# ProPrj_SunLight.net
KiCad netlist of a schematic drawn in EasyEDA Pro
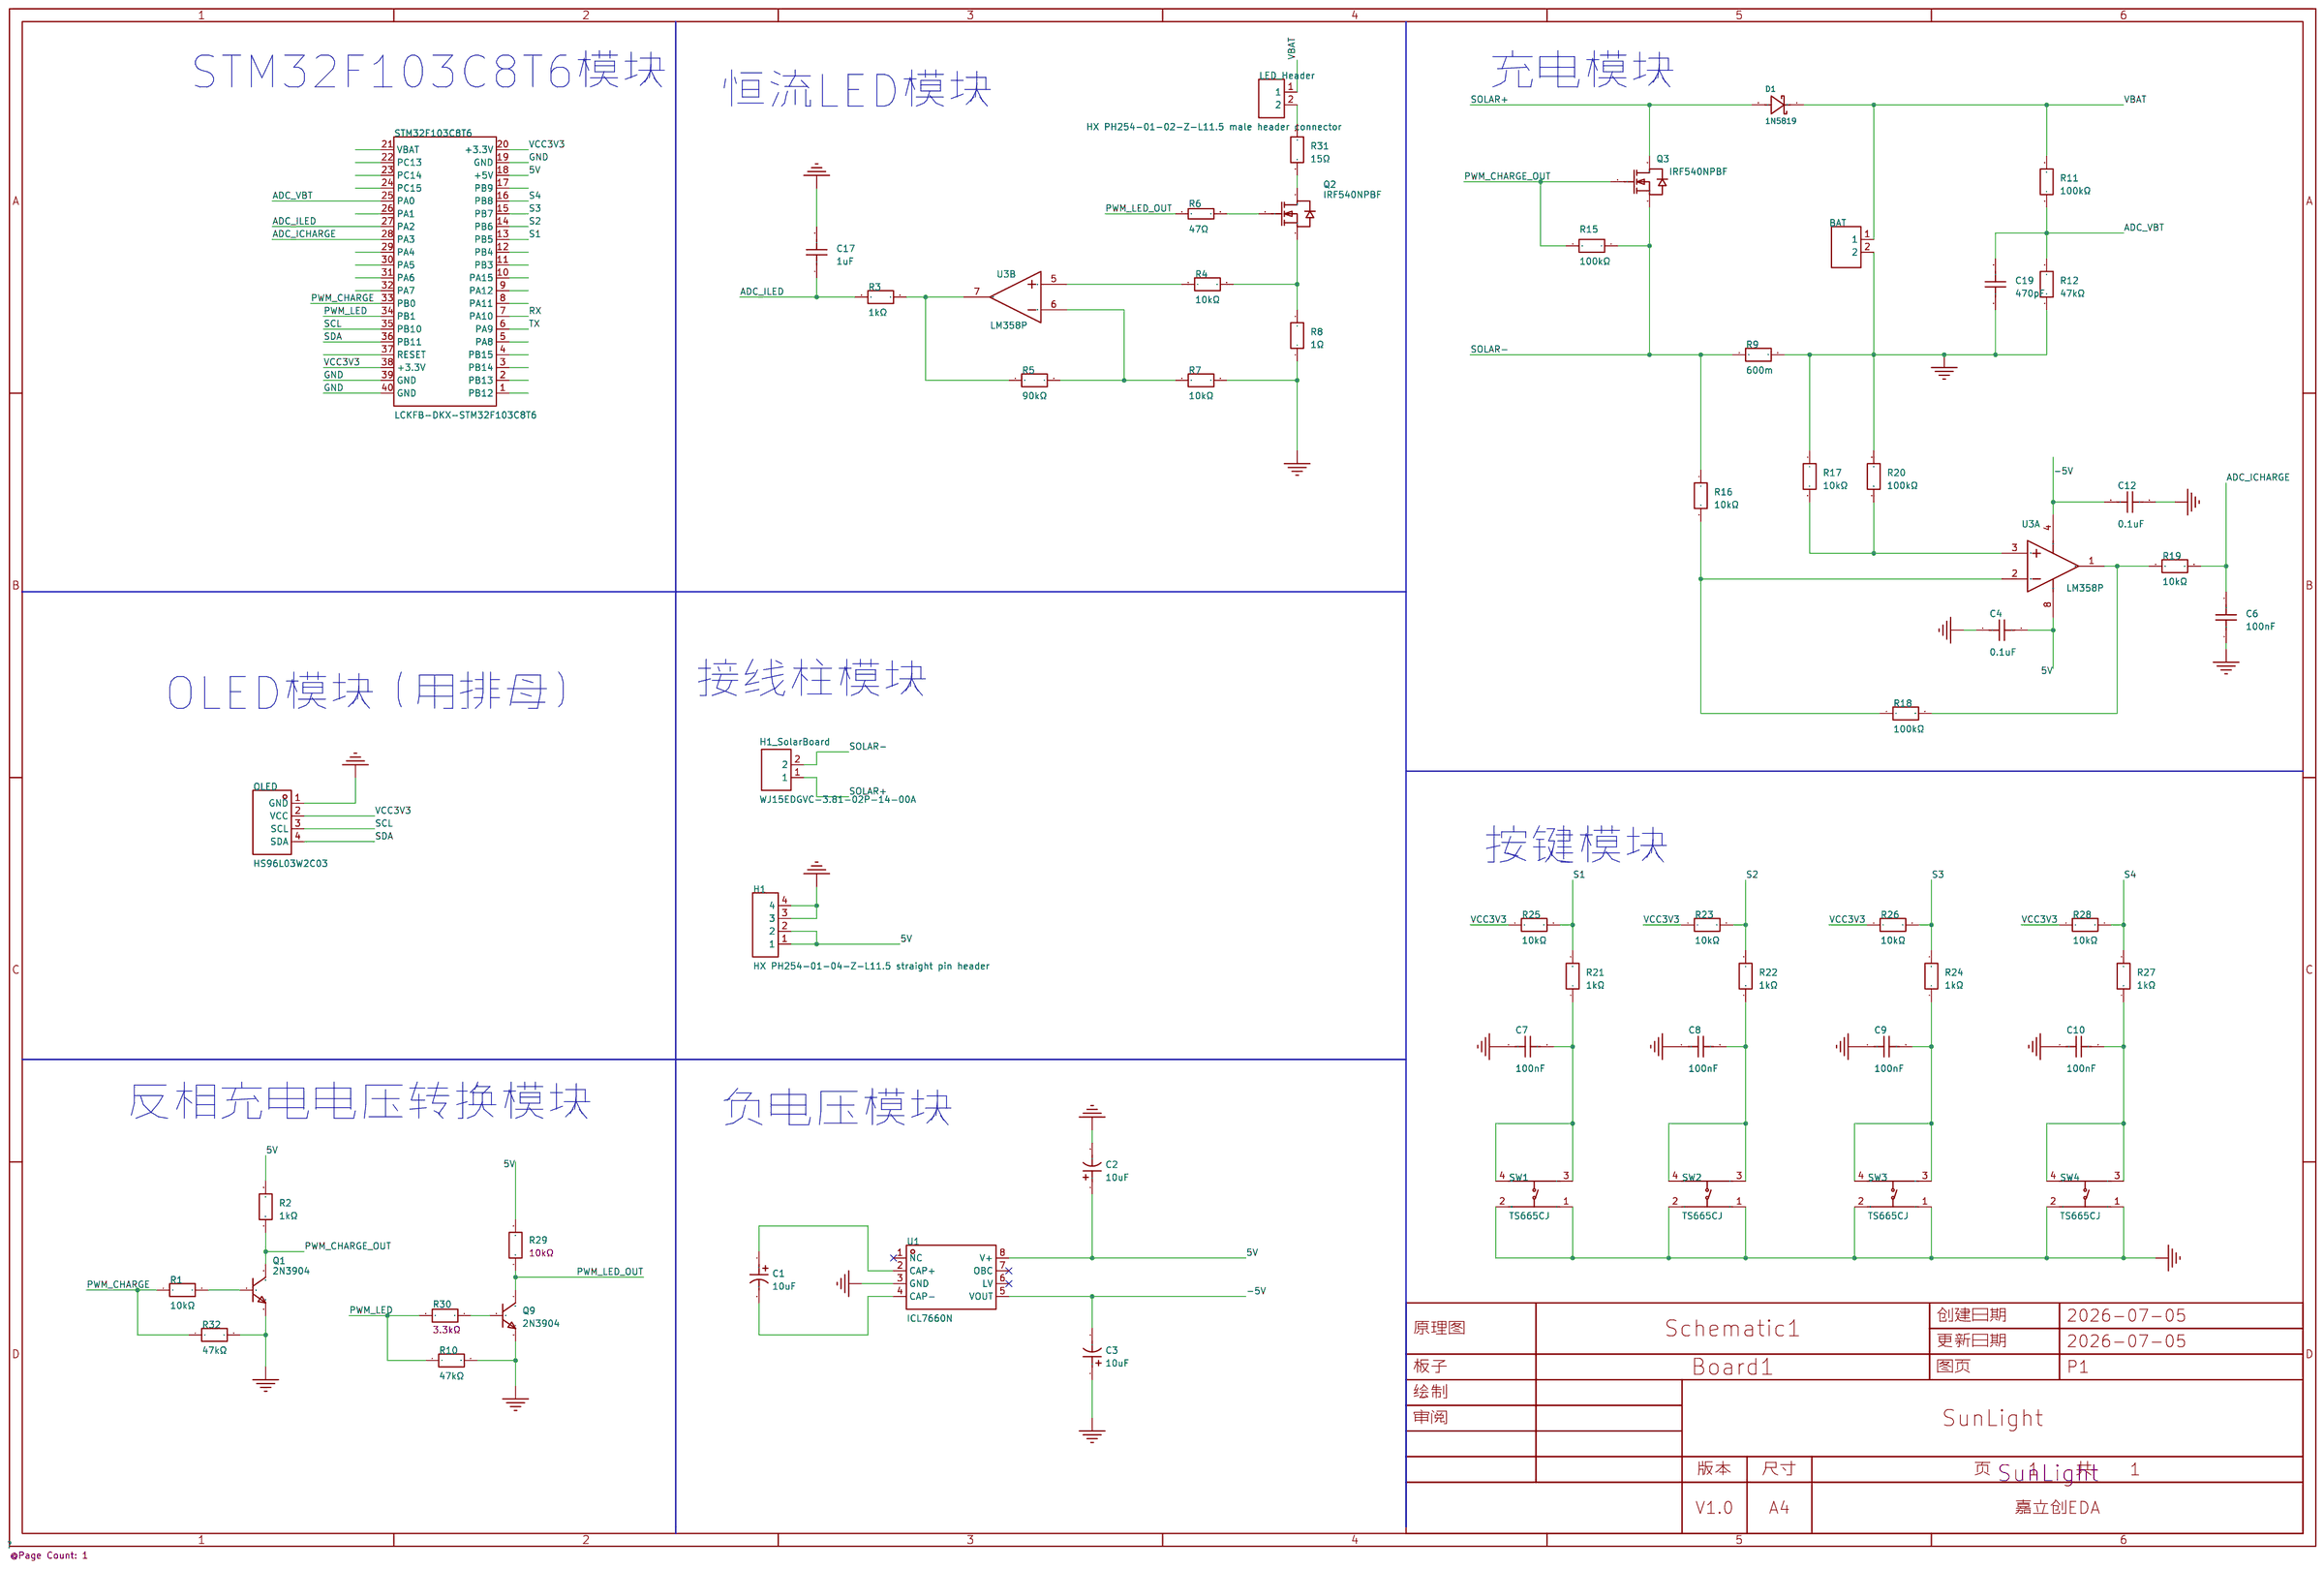
[diagram p0: schematic sheet]

(export (version "E")
  (design (tool "Eeschema 10.0.6"))
  (components
    (comp (ref "BAT")
      (value "WJ15EDGVC-3.81-02P-14-00A")
      (footprint "easyedapro:CONN-TH_WJ15EDGVC-3.81-2P")
      (fields (field (name "Manufacturer") "KANGNEX(康奈克斯电气)"))
      (libsource (lib "easyedapro") (part "WJ15EDGVC-3.81-2P"))
    )
    (comp (ref "C1")
      (value "10uF")
      (footprint "easyedapro:CAP-TH_BD10.0-P5.00-D0.6-FD_1")
      (fields (field (name "Manufacturer Part") "ERG450V10M10x16") (field (name "Manufacturer") "JIERR(捷而瑞)"))
      (libsource (lib "easyedapro") (part "ERG450V10M10X16"))
    )
    (comp (ref "C2")
      (value "10uF")
      (footprint "easyedapro:CAP-TH_BD10.0-P5.00-D0.6-FD_1")
      (fields (field (name "Manufacturer Part") "ERG450V10M10x16") (field (name "Manufacturer") "JIERR(捷而瑞)"))
      (libsource (lib "easyedapro") (part "ERG450V10M10X16"))
    )
    (comp (ref "C3")
      (value "10uF")
      (footprint "easyedapro:CAP-TH_BD10.0-P5.00-D0.6-FD_1")
      (fields (field (name "Manufacturer Part") "ERG450V10M10x16") (field (name "Manufacturer") "JIERR(捷而瑞)"))
      (libsource (lib "easyedapro") (part "ERG450V10M10X16"))
    )
    (comp (ref "C4")
      (value "0.1uF")
      (footprint "easyedapro:CAP-TH_L5.3-W3.2-P2.54-D0.6-S2.65")
      (description "容值:100nF;精度:-20%~+80%;额定电压:50V;温度系数:Y5V;")
      (fields
        (field (name "Manufacturer Part") "CC1H104ZA1ED3F5O1100")
        (field (name "Manufacturer") "Dersonic(德尔创)")
      )
      (libsource (lib "easyedapro") (part "CC1H104ZA1ED3F5O1100"))
    )
    (comp (ref "C6")
      (value "100nF")
      (footprint "easyedapro:CAP-TH_L5.5-W4.0-P5.00-D0.5")
      (fields
        (field (name "Manufacturer Part") "Y5P102K2KV16CC0224")
        (field (name "Manufacturer") "KNSCHA(科尼盛)")
      )
      (libsource (lib "easyedapro") (part "Y5P102K2KV16CC0224"))
    )
    (comp (ref "C7")
      (value "100nF")
      (footprint "easyedapro:CAP-TH_L5.5-W4.0-P5.00-D0.5")
      (fields
        (field (name "Manufacturer Part") "Y5P102K2KV16CC0224")
        (field (name "Manufacturer") "KNSCHA(科尼盛)")
      )
      (libsource (lib "easyedapro") (part "Y5P102K2KV16CC0224"))
    )
    (comp (ref "C8")
      (value "100nF")
      (footprint "easyedapro:CAP-TH_L5.5-W4.0-P5.00-D0.5")
      (fields
        (field (name "Manufacturer Part") "Y5P102K2KV16CC0224")
        (field (name "Manufacturer") "KNSCHA(科尼盛)")
      )
      (libsource (lib "easyedapro") (part "Y5P102K2KV16CC0224"))
    )
    (comp (ref "C9")
      (value "100nF")
      (footprint "easyedapro:CAP-TH_L5.5-W4.0-P5.00-D0.5")
      (fields
        (field (name "Manufacturer Part") "Y5P102K2KV16CC0224")
        (field (name "Manufacturer") "KNSCHA(科尼盛)")
      )
      (libsource (lib "easyedapro") (part "Y5P102K2KV16CC0224"))
    )
    (comp (ref "C10")
      (value "100nF")
      (footprint "easyedapro:CAP-TH_L5.5-W4.0-P5.00-D0.5")
      (fields
        (field (name "Manufacturer Part") "Y5P102K2KV16CC0224")
        (field (name "Manufacturer") "KNSCHA(科尼盛)")
      )
      (libsource (lib "easyedapro") (part "Y5P102K2KV16CC0224"))
    )
    (comp (ref "C12")
      (value "0.1uF")
      (footprint "easyedapro:CAP-TH_L5.3-W3.2-P2.54-D0.6-S2.65")
      (description "容值:100nF;精度:-20%~+80%;额定电压:50V;温度系数:Y5V;")
      (fields
        (field (name "Manufacturer Part") "CC1H104ZA1ED3F5O1100")
        (field (name "Manufacturer") "Dersonic(德尔创)")
      )
      (libsource (lib "easyedapro") (part "CC1H104ZA1ED3F5O1100"))
    )
    (comp (ref "C17")
      (value "1uF")
      (footprint "easyedapro:CAP-TH_L5.8-W2.8")
      (fields
        (field (name "Manufacturer Part") "CC1H104MC1FD3F6C10SA")
        (field (name "Manufacturer") "Dersonic(德尔创)")
      )
      (libsource (lib "easyedapro") (part "CC1H104MC1FD3F6C10SA"))
    )
    (comp (ref "C19")
      (value "470pF")
      (footprint "easyedapro:CAP-TH_L5.5-W4.0-P5.00-D0.5")
      (fields
        (field (name "Manufacturer Part") "Y5P102K2KV16CC0224")
        (field (name "Manufacturer") "KNSCHA(科尼盛)")
      )
      (libsource (lib "easyedapro") (part "Y5P102K2KV16CC0224"))
    )
    (comp (ref "D1")
      (value "1N5819")
      (footprint "easyedapro:DO-41_BD2.4-L4.7-P8.70-D0.9-RD")
      (fields (field (name "Manufacturer") "R+O(宏嘉诚)"))
      (libsource (lib "easyedapro") (part "1N5819_C54795756"))
    )
    (comp (ref "H1")
      (value "HX PH254-01-04-Z-L11.5 straight pin header")
      (footprint "easyedapro:HDR-TH_4P-HX-PH254-01-04-Z-L11.5")
      (fields (field (name "Manufacturer") "hanxia(韩下)"))
      (libsource (lib "easyedapro") (part "HX PH254-01-04-Z-L11.5 STRAIGHT PIN HEADER"))
    )
    (comp (ref "H1_SolarBoard")
      (value "WJ15EDGVC-3.81-02P-14-00A")
      (footprint "easyedapro:CONN-TH_WJ15EDGVC-3.81-2P")
      (fields (field (name "Manufacturer") "KANGNEX(康奈克斯电气)"))
      (libsource (lib "easyedapro") (part "WJ15EDGVC-3.81-2P"))
    )
    (comp (ref "LED_Header")
      (value "HX PH254-01-02-Z-L11.5 male header connector")
      (footprint "easyedapro:HDR-TH_2P-P2.54-V-M")
      (fields (field (name "Manufacturer") "hanxia(韩下)"))
      (libsource (lib "easyedapro") (part "HX PH254-01-02-Z-L11.5 MALE HEADER CONNECTOR"))
    )
    (comp (ref "OLED")
      (value "HS96L03W2C03")
      (footprint "easyedapro:OLED-TH_L27.8-W27.2-P2.54_C9900033791")
      (description "核心芯片:SSD1315芯片;接口类型:I2C;尺寸(inch):0.96;像素分辨率:128x64;")
      (fields (field (name "Manufacturer") "HS(汉昇)"))
      (libsource (lib "easyedapro") (part "HS96L03W2C03"))
    )
    (comp (ref "Q1")
      (value "2N3904")
      (footprint "easyedapro:TO-92-3_L4.6-W3.6-P1.27-L_1")
      (fields (field (name "Manufacturer") "JSMSEMI(杰盛微)"))
      (libsource (lib "easyedapro") (part "2N3904_C2874602"))
    )
    (comp (ref "Q2")
      (value "IRF540NPBF")
      (footprint "easyedapro:TO-220-3_L10.0-W4.5-P2.54-L")
      (fields (field (name "Manufacturer") "Infineon(英飞凌)"))
      (libsource (lib "easyedapro") (part "IRF540NPBF"))
    )
    (comp (ref "Q3")
      (value "IRF540NPBF")
      (footprint "easyedapro:TO-220-3_L10.0-W4.5-P2.54-L")
      (fields (field (name "Manufacturer") "Infineon(英飞凌)"))
      (libsource (lib "easyedapro") (part "IRF540NPBF"))
    )
    (comp (ref "Q9")
      (value "2N3904")
      (footprint "easyedapro:TO-92-3_L4.6-W3.6-P1.27-L_1")
      (description "晶体管类型:NPN;集电极电流(Ic):200mA;集射极击穿电压(Vceo):40V;耗散功率(Pd):625mW;直流电流增益(hFE):-;")
      (fields (field (name "Manufacturer") "JSMSEMI(杰盛微)"))
      (libsource (lib "easyedapro") (part "2N3904_C2874602"))
    )
    (comp (ref "R1")
      (value "10kΩ")
      (footprint "easyedapro:RES-TH_BD2.7-L6.2-P10.20-D0.4")
      (description "电阻类型:金属膜电阻;阻值:1kΩ;精度:±1%;功率:250mW;温度系数:±100ppm/℃;")
      (fields (field (name "Manufacturer Part") "MF1/4W-1K±1%-ST52") (field (name "Manufacturer") "VO(翔胜)"))
      (libsource (lib "easyedapro") (part "MF1/4W-1K±1%-ST52"))
    )
    (comp (ref "R2")
      (value "1kΩ")
      (footprint "easyedapro:RES-TH_BD2.7-L6.2-P10.20-D0.4")
      (description "电阻类型:金属膜电阻;阻值:1kΩ;精度:±1%;功率:250mW;温度系数:±100ppm/℃;")
      (fields (field (name "Manufacturer Part") "MF1/4W-1K±1%-ST52") (field (name "Manufacturer") "VO(翔胜)"))
      (libsource (lib "easyedapro") (part "MF1/4W-1K±1%-ST52"))
    )
    (comp (ref "R3")
      (value "1kΩ")
      (footprint "easyedapro:RES-TH_BD2.7-L6.2-P10.20-D0.4")
      (description "电阻类型:金属膜电阻;阻值:1kΩ;精度:±1%;功率:250mW;温度系数:±100ppm/℃;")
      (fields (field (name "Manufacturer Part") "MF1/4W-1K±1%-ST52") (field (name "Manufacturer") "VO(翔胜)"))
      (libsource (lib "easyedapro") (part "MF1/4W-1K±1%-ST52"))
    )
    (comp (ref "R4")
      (value "10kΩ")
      (footprint "easyedapro:RES-TH_BD2.7-L6.2-P10.20-D0.4")
      (description "电阻类型:金属膜电阻;阻值:1kΩ;精度:±1%;功率:250mW;温度系数:±100ppm/℃;")
      (fields (field (name "Manufacturer Part") "MF1/4W-1K±1%-ST52") (field (name "Manufacturer") "VO(翔胜)"))
      (libsource (lib "easyedapro") (part "MF1/4W-1K±1%-ST52"))
    )
    (comp (ref "R5")
      (value "90kΩ")
      (footprint "easyedapro:RES-TH_BD2.7-L6.2-P10.20-D0.4")
      (description "电阻类型:金属膜电阻;阻值:1kΩ;精度:±1%;功率:250mW;温度系数:±100ppm/℃;")
      (fields (field (name "Manufacturer Part") "MF1/4W-1K±1%-ST52") (field (name "Manufacturer") "VO(翔胜)"))
      (libsource (lib "easyedapro") (part "MF1/4W-1K±1%-ST52"))
    )
    (comp (ref "R6")
      (value "47Ω")
      (footprint "easyedapro:RES-TH_BD2.4-L6.3-P10.30-D0.6")
      (fields (field (name "Manufacturer Part") "MFR-25FTE52-47R") (field (name "Manufacturer") "YAGEO(国巨)"))
      (libsource (lib "easyedapro") (part "MFR-25FTE52-47R"))
    )
    (comp (ref "R7")
      (value "10kΩ")
      (footprint "easyedapro:RES-TH_BD2.7-L6.2-P10.20-D0.4")
      (description "电阻类型:金属膜电阻;阻值:1kΩ;精度:±1%;功率:250mW;温度系数:±100ppm/℃;")
      (fields (field (name "Manufacturer Part") "MF1/4W-1K±1%-ST52") (field (name "Manufacturer") "VO(翔胜)"))
      (libsource (lib "easyedapro") (part "MF1/4W-1K±1%-ST52"))
    )
    (comp (ref "R8")
      (value "1Ω")
      (footprint "easyedapro:RES-TH_BD2.7-L6.2-P10.20-D0.4")
      (description "电阻类型:金属膜电阻;阻值:1kΩ;精度:±1%;功率:250mW;温度系数:±100ppm/℃;")
      (fields (field (name "Manufacturer Part") "MF1/4W-1K±1%-ST52") (field (name "Manufacturer") "VO(翔胜)"))
      (libsource (lib "easyedapro") (part "MF1/4W-1K±1%-ST52"))
    )
    (comp (ref "R9")
      (value "600m")
      (footprint "easyedapro:RES-TH_BD2.7-L6.2-P10.20-D0.4")
      (description "电阻类型:金属膜电阻;阻值:1kΩ;精度:±1%;功率:250mW;温度系数:±100ppm/℃;")
      (fields (field (name "Manufacturer Part") "MF1/4W-1K±1%-ST52") (field (name "Manufacturer") "VO(翔胜)"))
      (libsource (lib "easyedapro") (part "MF1/4W-1K±1%-ST52"))
    )
    (comp (ref "R10")
      (value "47kΩ")
      (footprint "easyedapro:RES-TH_BD2.7-L6.2-P10.20-D0.4")
      (fields (field (name "Manufacturer Part") "MF1/4W-47K±1%-ST52") (field (name "Manufacturer") "VO(翔胜)"))
      (libsource (lib "easyedapro") (part "MF1/4W-47K±1%-ST52"))
    )
    (comp (ref "R11")
      (value "100kΩ")
      (footprint "easyedapro:RES-TH_BD2.7-L6.2-P10.20-D0.4")
      (description "电阻类型:金属膜电阻;阻值:1kΩ;精度:±1%;功率:250mW;温度系数:±100ppm/℃;")
      (fields (field (name "Manufacturer Part") "MF1/4W-1K±1%-ST52") (field (name "Manufacturer") "VO(翔胜)"))
      (libsource (lib "easyedapro") (part "MF1/4W-1K±1%-ST52"))
    )
    (comp (ref "R12")
      (value "47kΩ")
      (footprint "easyedapro:RES-TH_BD2.7-L6.2-P10.20-D0.4")
      (description "电阻类型:金属膜电阻;阻值:1kΩ;精度:±1%;功率:250mW;温度系数:±100ppm/℃;")
      (fields (field (name "Manufacturer Part") "MF1/4W-1K±1%-ST52") (field (name "Manufacturer") "VO(翔胜)"))
      (libsource (lib "easyedapro") (part "MF1/4W-1K±1%-ST52"))
    )
    (comp (ref "R15")
      (value "100kΩ")
      (footprint "easyedapro:RES-TH_BD2.7-L6.2-P10.20-D0.4")
      (description "电阻类型:金属膜电阻;阻值:1kΩ;精度:±1%;功率:250mW;温度系数:±100ppm/℃;")
      (fields (field (name "Manufacturer Part") "MF1/4W-1K±1%-ST52") (field (name "Manufacturer") "VO(翔胜)"))
      (libsource (lib "easyedapro") (part "MF1/4W-1K±1%-ST52"))
    )
    (comp (ref "R16")
      (value "10kΩ")
      (footprint "easyedapro:RES-TH_BD2.7-L6.2-P10.20-D0.4")
      (description "电阻类型:金属膜电阻;阻值:1kΩ;精度:±1%;功率:250mW;温度系数:±100ppm/℃;")
      (fields (field (name "Manufacturer Part") "MF1/4W-1K±1%-ST52") (field (name "Manufacturer") "VO(翔胜)"))
      (libsource (lib "easyedapro") (part "MF1/4W-1K±1%-ST52"))
    )
    (comp (ref "R17")
      (value "10kΩ")
      (footprint "easyedapro:RES-TH_BD2.7-L6.2-P10.20-D0.4")
      (description "电阻类型:金属膜电阻;阻值:1kΩ;精度:±1%;功率:250mW;温度系数:±100ppm/℃;")
      (fields (field (name "Manufacturer Part") "MF1/4W-1K±1%-ST52") (field (name "Manufacturer") "VO(翔胜)"))
      (libsource (lib "easyedapro") (part "MF1/4W-1K±1%-ST52"))
    )
    (comp (ref "R18")
      (value "100kΩ")
      (footprint "easyedapro:RES-TH_BD2.7-L6.2-P10.20-D0.4")
      (description "电阻类型:金属膜电阻;阻值:1kΩ;精度:±1%;功率:250mW;温度系数:±100ppm/℃;")
      (fields (field (name "Manufacturer Part") "MF1/4W-1K±1%-ST52") (field (name "Manufacturer") "VO(翔胜)"))
      (libsource (lib "easyedapro") (part "MF1/4W-1K±1%-ST52"))
    )
    (comp (ref "R19")
      (value "10kΩ")
      (footprint "easyedapro:RES-TH_BD2.7-L6.2-P10.20-D0.4")
      (description "电阻类型:金属膜电阻;阻值:1kΩ;精度:±1%;功率:250mW;温度系数:±100ppm/℃;")
      (fields (field (name "Manufacturer Part") "MF1/4W-1K±1%-ST52") (field (name "Manufacturer") "VO(翔胜)"))
      (libsource (lib "easyedapro") (part "MF1/4W-1K±1%-ST52"))
    )
    (comp (ref "R20")
      (value "100kΩ")
      (footprint "easyedapro:RES-TH_BD2.7-L6.2-P10.20-D0.4")
      (description "电阻类型:金属膜电阻;阻值:1kΩ;精度:±1%;功率:250mW;温度系数:±100ppm/℃;")
      (fields (field (name "Manufacturer Part") "MF1/4W-1K±1%-ST52") (field (name "Manufacturer") "VO(翔胜)"))
      (libsource (lib "easyedapro") (part "MF1/4W-1K±1%-ST52"))
    )
    (comp (ref "R21")
      (value "1kΩ")
      (footprint "easyedapro:RES-TH_BD2.7-L6.2-P10.20-D0.4")
      (description "电阻类型:金属膜电阻;阻值:1kΩ;精度:±1%;功率:250mW;温度系数:±100ppm/℃;")
      (fields (field (name "Manufacturer Part") "MF1/4W-1K±1%-ST52") (field (name "Manufacturer") "VO(翔胜)"))
      (libsource (lib "easyedapro") (part "MF1/4W-1K±1%-ST52"))
    )
    (comp (ref "R22")
      (value "1kΩ")
      (footprint "easyedapro:RES-TH_BD2.7-L6.2-P10.20-D0.4")
      (description "电阻类型:金属膜电阻;阻值:1kΩ;精度:±1%;功率:250mW;温度系数:±100ppm/℃;")
      (fields (field (name "Manufacturer Part") "MF1/4W-1K±1%-ST52") (field (name "Manufacturer") "VO(翔胜)"))
      (libsource (lib "easyedapro") (part "MF1/4W-1K±1%-ST52"))
    )
    (comp (ref "R23")
      (value "10kΩ")
      (footprint "easyedapro:RES-TH_BD2.7-L6.2-P10.20-D0.4")
      (description "电阻类型:金属膜电阻;阻值:1kΩ;精度:±1%;功率:250mW;温度系数:±100ppm/℃;")
      (fields (field (name "Manufacturer Part") "MF1/4W-1K±1%-ST52") (field (name "Manufacturer") "VO(翔胜)"))
      (libsource (lib "easyedapro") (part "MF1/4W-1K±1%-ST52"))
    )
    (comp (ref "R24")
      (value "1kΩ")
      (footprint "easyedapro:RES-TH_BD2.7-L6.2-P10.20-D0.4")
      (description "电阻类型:金属膜电阻;阻值:1kΩ;精度:±1%;功率:250mW;温度系数:±100ppm/℃;")
      (fields (field (name "Manufacturer Part") "MF1/4W-1K±1%-ST52") (field (name "Manufacturer") "VO(翔胜)"))
      (libsource (lib "easyedapro") (part "MF1/4W-1K±1%-ST52"))
    )
    (comp (ref "R25")
      (value "10kΩ")
      (footprint "easyedapro:RES-TH_BD2.7-L6.2-P10.20-D0.4")
      (description "电阻类型:金属膜电阻;阻值:1kΩ;精度:±1%;功率:250mW;温度系数:±100ppm/℃;")
      (fields (field (name "Manufacturer Part") "MF1/4W-1K±1%-ST52") (field (name "Manufacturer") "VO(翔胜)"))
      (libsource (lib "easyedapro") (part "MF1/4W-1K±1%-ST52"))
    )
    (comp (ref "R26")
      (value "10kΩ")
      (footprint "easyedapro:RES-TH_BD2.7-L6.2-P10.20-D0.4")
      (description "电阻类型:金属膜电阻;阻值:1kΩ;精度:±1%;功率:250mW;温度系数:±100ppm/℃;")
      (fields (field (name "Manufacturer Part") "MF1/4W-1K±1%-ST52") (field (name "Manufacturer") "VO(翔胜)"))
      (libsource (lib "easyedapro") (part "MF1/4W-1K±1%-ST52"))
    )
    (comp (ref "R27")
      (value "1kΩ")
      (footprint "easyedapro:RES-TH_BD2.7-L6.2-P10.20-D0.4")
      (description "电阻类型:金属膜电阻;阻值:1kΩ;精度:±1%;功率:250mW;温度系数:±100ppm/℃;")
      (fields (field (name "Manufacturer Part") "MF1/4W-1K±1%-ST52") (field (name "Manufacturer") "VO(翔胜)"))
      (libsource (lib "easyedapro") (part "MF1/4W-1K±1%-ST52"))
    )
    (comp (ref "R28")
      (value "10kΩ")
      (footprint "easyedapro:RES-TH_BD2.7-L6.2-P10.20-D0.4")
      (description "电阻类型:金属膜电阻;阻值:1kΩ;精度:±1%;功率:250mW;温度系数:±100ppm/℃;")
      (fields (field (name "Manufacturer Part") "MF1/4W-1K±1%-ST52") (field (name "Manufacturer") "VO(翔胜)"))
      (libsource (lib "easyedapro") (part "MF1/4W-1K±1%-ST52"))
    )
    (comp (ref "R29")
      (value "1kΩ")
      (footprint "easyedapro:RES-TH_BD2.7-L6.2-P10.20-D0.4")
      (description "电阻类型:金属膜电阻;阻值:1kΩ;精度:±1%;功率:250mW;温度系数:±100ppm/℃;")
      (fields
        (field (name "Manufacturer Part") "MF1/4W-1K±1%-ST52")
        (field (name "Manufacturer") "VO(翔胜)")
        (field (name "Resistance") "10kΩ")
      )
      (libsource (lib "easyedapro") (part "MF1/4W-1K±1%-ST52"))
    )
    (comp (ref "R30")
      (value "1kΩ")
      (footprint "easyedapro:RES-TH_BD2.7-L6.2-P10.20-D0.4")
      (description "电阻类型:金属膜电阻;阻值:1kΩ;精度:±1%;功率:250mW;温度系数:±100ppm/℃;")
      (fields
        (field (name "Manufacturer Part") "MF1/4W-1K±1%-ST52")
        (field (name "Manufacturer") "VO(翔胜)")
        (field (name "Resistance") "3.3kΩ")
      )
      (libsource (lib "easyedapro") (part "MF1/4W-1K±1%-ST52"))
    )
    (comp (ref "R31")
      (value "15Ω")
      (footprint "easyedapro:RES-TH_BD2.7-L6.2-P10.20-D0.4")
      (fields (field (name "Manufacturer Part") "MF1/4W-4Ω7±1%-OT26") (field (name "Manufacturer") "VO(翔胜)"))
      (libsource (lib "easyedapro") (part "MF1/4W-4Ω7±1%-OT26"))
    )
    (comp (ref "R32")
      (value "47kΩ")
      (footprint "easyedapro:RES-TH_BD2.7-L6.2-P10.20-D0.4")
      (fields (field (name "Manufacturer Part") "MF1/4W-47K±1%-ST52") (field (name "Manufacturer") "VO(翔胜)"))
      (libsource (lib "easyedapro") (part "MF1/4W-47K±1%-ST52"))
    )
    (comp (ref "STM32F103C8T6")
      (value "LCKFB-DKX-STM32F103C8T6")
      (footprint "easyedapro:CONN-TH_L53.3-W22.9_STM32F103C8T6-CARD")
      (fields (field (name "Manufacturer") "立创开发板"))
      (libsource (lib "easyedapro") (part "LCKFB-DKX-STM32F103C8T6"))
    )
    (comp (ref "SW1")
      (value "TS665CJ")
      (footprint "easyedapro:SW-TH_4P-L6.0-W6.0-P4.50-LS6.5")
      (fields (field (name "Manufacturer") "SHOU HAN(首韩)"))
      (libsource (lib "easyedapro") (part "TS665CJ"))
    )
    (comp (ref "SW2")
      (value "TS665CJ")
      (footprint "easyedapro:SW-TH_4P-L6.0-W6.0-P4.50-LS6.5")
      (fields (field (name "Manufacturer") "SHOU HAN(首韩)"))
      (libsource (lib "easyedapro") (part "TS665CJ"))
    )
    (comp (ref "SW3")
      (value "TS665CJ")
      (footprint "easyedapro:SW-TH_4P-L6.0-W6.0-P4.50-LS6.5")
      (fields (field (name "Manufacturer") "SHOU HAN(首韩)"))
      (libsource (lib "easyedapro") (part "TS665CJ"))
    )
    (comp (ref "SW4")
      (value "TS665CJ")
      (footprint "easyedapro:SW-TH_4P-L6.0-W6.0-P4.50-LS6.5")
      (fields (field (name "Manufacturer") "SHOU HAN(首韩)"))
      (libsource (lib "easyedapro") (part "TS665CJ"))
    )
    (comp (ref "U1")
      (value "ICL7660N")
      (footprint "easyedapro:DIP-8_L9.4-W6.4-P2.54-LS9.1-BL")
      (fields (field (name "Manufacturer") "HGSEMI(华冠)"))
      (libsource (lib "easyedapro") (part "ICL7660N"))
    )
    (comp (ref "U3")
      (value "LM358P")
      (footprint "easyedapro:DIP-8_L9.7-W6.4-P2.54-LS7.6-BL")
      (description "放大器数:2;轨到轨:-;增益带宽积(GBW):1MHz;输入失调电压(Vos):2mV;压摆率(SR):-;输入偏置电流(Ib):45nA;")
      (fields (field (name "Manufacturer") "Slkor(萨科微)"))
      (libsource (lib "easyedapro") (part "LM358P_C5330384"))
    )
  )
  (nets
    (net (code "1") (name "/-5V") (class "Default")
      (node (ref "C12") (pin "2") (pinfunction "2_2") (pintype "unspecified"))
      (node (ref "C3") (pin "2") (pinfunction "2_2") (pintype "input"))
      (node (ref "U1") (pin "5") (pinfunction "VOUT_5") (pintype "unspecified"))
      (node (ref "U3") (pin "4") (pinfunction "GND_4") (pintype "unspecified"))
    )
    (net (code "2") (name "/5V") (class "Default")
      (node (ref "C2") (pin "1") (pinfunction "1_1") (pintype "input"))
      (node (ref "C4") (pin "2") (pinfunction "2_2") (pintype "unspecified"))
      (node (ref "H1") (pin "1") (pinfunction "1_1") (pintype "unspecified"))
      (node (ref "H1") (pin "2") (pinfunction "2_2") (pintype "unspecified"))
      (node (ref "R2") (pin "2") (pinfunction "2_2") (pintype "unspecified"))
      (node (ref "R29") (pin "2") (pinfunction "2_2") (pintype "unspecified"))
      (node (ref "STM32F103C8T6") (pin "18") (pinfunction "+5V_18") (pintype "unspecified"))
      (node (ref "U1") (pin "8") (pinfunction "V+_8") (pintype "unspecified"))
      (node (ref "U3") (pin "8") (pinfunction "VCC_8") (pintype "unspecified"))
    )
    (net (code "3") (name "/ADC_ICHARGE") (class "Default")
      (node (ref "C6") (pin "2") (pinfunction "2_2") (pintype "unspecified"))
      (node (ref "R19") (pin "2") (pinfunction "2_2") (pintype "unspecified"))
      (node (ref "STM32F103C8T6") (pin "28") (pinfunction "PA3_28") (pintype "unspecified"))
    )
    (net (code "4") (name "/ADC_ILED") (class "Default")
      (node (ref "C17") (pin "1") (pinfunction "1_1") (pintype "unspecified"))
      (node (ref "R3") (pin "1") (pinfunction "1_1") (pintype "unspecified"))
      (node (ref "STM32F103C8T6") (pin "27") (pinfunction "PA2_27") (pintype "unspecified"))
    )
    (net (code "5") (name "/ADC_VBT") (class "Default")
      (node (ref "C19") (pin "2") (pinfunction "2_2") (pintype "unspecified"))
      (node (ref "R11") (pin "1") (pinfunction "1_1") (pintype "unspecified"))
      (node (ref "R12") (pin "2") (pinfunction "2_2") (pintype "unspecified"))
      (node (ref "STM32F103C8T6") (pin "25") (pinfunction "PA0_25") (pintype "unspecified"))
    )
    (net (code "6") (name "/PWM_CHARGE") (class "Default")
      (node (ref "R1") (pin "1") (pinfunction "1_1") (pintype "unspecified"))
      (node (ref "R32") (pin "1") (pinfunction "1_1") (pintype "unspecified"))
      (node (ref "STM32F103C8T6") (pin "33") (pinfunction "PB0_33") (pintype "unspecified"))
    )
    (net (code "7") (name "/PWM_CHARGE_OUT") (class "Default")
      (node (ref "Q1") (pin "1") (pinfunction "C_1") (pintype "unspecified"))
      (node (ref "Q3") (pin "1") (pinfunction "G_1") (pintype "unspecified"))
      (node (ref "R15") (pin "2") (pinfunction "2_2") (pintype "unspecified"))
      (node (ref "R2") (pin "1") (pinfunction "1_1") (pintype "unspecified"))
    )
    (net (code "8") (name "/PWM_LED") (class "Default")
      (node (ref "R10") (pin "1") (pinfunction "1_1") (pintype "unspecified"))
      (node (ref "R30") (pin "2") (pinfunction "2_2") (pintype "unspecified"))
      (node (ref "STM32F103C8T6") (pin "34") (pinfunction "PB1_34") (pintype "unspecified"))
    )
    (net (code "9") (name "/PWM_LED_OUT") (class "Default")
      (node (ref "Q9") (pin "1") (pinfunction "C_1") (pintype "unspecified"))
      (node (ref "R29") (pin "1") (pinfunction "1_1") (pintype "unspecified"))
      (node (ref "R6") (pin "1") (pinfunction "1_1") (pintype "unspecified"))
    )
    (net (code "10") (name "/RX") (class "Default")
      (node (ref "STM32F103C8T6") (pin "7") (pinfunction "PA10_7") (pintype "unspecified"))
    )
    (net (code "11") (name "/S1") (class "Default")
      (node (ref "R21") (pin "2") (pinfunction "2_2") (pintype "unspecified"))
      (node (ref "R25") (pin "2") (pinfunction "2_2") (pintype "unspecified"))
      (node (ref "STM32F103C8T6") (pin "13") (pinfunction "PB5_13") (pintype "unspecified"))
    )
    (net (code "12") (name "/S2") (class "Default")
      (node (ref "R22") (pin "2") (pinfunction "2_2") (pintype "unspecified"))
      (node (ref "R23") (pin "2") (pinfunction "2_2") (pintype "unspecified"))
      (node (ref "STM32F103C8T6") (pin "14") (pinfunction "PB6_14") (pintype "unspecified"))
    )
    (net (code "13") (name "/S3") (class "Default")
      (node (ref "R24") (pin "2") (pinfunction "2_2") (pintype "unspecified"))
      (node (ref "R26") (pin "2") (pinfunction "2_2") (pintype "unspecified"))
      (node (ref "STM32F103C8T6") (pin "15") (pinfunction "PB7_15") (pintype "unspecified"))
    )
    (net (code "14") (name "/S4") (class "Default")
      (node (ref "R27") (pin "2") (pinfunction "2_2") (pintype "unspecified"))
      (node (ref "R28") (pin "2") (pinfunction "2_2") (pintype "unspecified"))
      (node (ref "STM32F103C8T6") (pin "16") (pinfunction "PB8_16") (pintype "unspecified"))
    )
    (net (code "15") (name "/SCL") (class "Default")
      (node (ref "OLED") (pin "3") (pinfunction "SCL_3") (pintype "unspecified"))
      (node (ref "STM32F103C8T6") (pin "35") (pinfunction "PB10_35") (pintype "unspecified"))
    )
    (net (code "16") (name "/SDA") (class "Default")
      (node (ref "OLED") (pin "4") (pinfunction "SDA_4") (pintype "unspecified"))
      (node (ref "STM32F103C8T6") (pin "36") (pinfunction "PB11_36") (pintype "unspecified"))
    )
    (net (code "17") (name "/SOLAR+") (class "Default")
      (node (ref "D1") (pin "2") (pinfunction "A_2") (pintype "unspecified"))
      (node (ref "H1_SolarBoard") (pin "1") (pinfunction "1_1") (pintype "unspecified"))
      (node (ref "Q3") (pin "2") (pinfunction "D_2") (pintype "unspecified"))
    )
    (net (code "18") (name "/SOLAR-") (class "Default")
      (node (ref "H1_SolarBoard") (pin "2") (pinfunction "2_2") (pintype "unspecified"))
      (node (ref "Q3") (pin "3") (pinfunction "S_3") (pintype "unspecified"))
      (node (ref "R15") (pin "1") (pinfunction "1_1") (pintype "unspecified"))
      (node (ref "R16") (pin "1") (pinfunction "1_1") (pintype "unspecified"))
      (node (ref "R9") (pin "1") (pinfunction "1_1") (pintype "unspecified"))
    )
    (net (code "19") (name "/TX") (class "Default")
      (node (ref "STM32F103C8T6") (pin "6") (pinfunction "PA9_6") (pintype "unspecified"))
    )
    (net (code "20") (name "/VBAT") (class "Default")
      (node (ref "BAT") (pin "1") (pinfunction "1_1") (pintype "unspecified"))
      (node (ref "D1") (pin "1") (pinfunction "C_1") (pintype "unspecified"))
      (node (ref "LED_Header") (pin "1") (pinfunction "1_1") (pintype "unspecified"))
      (node (ref "R11") (pin "2") (pinfunction "2_2") (pintype "unspecified"))
    )
    (net (code "21") (name "/VCC3V3") (class "Default")
      (node (ref "OLED") (pin "2") (pinfunction "VCC_2") (pintype "unspecified"))
      (node (ref "R23") (pin "1") (pinfunction "1_1") (pintype "unspecified"))
      (node (ref "R25") (pin "1") (pinfunction "1_1") (pintype "unspecified"))
      (node (ref "R26") (pin "1") (pinfunction "1_1") (pintype "unspecified"))
      (node (ref "R28") (pin "1") (pinfunction "1_1") (pintype "unspecified"))
      (node (ref "STM32F103C8T6") (pin "20") (pinfunction "+3.3V_20") (pintype "unspecified"))
      (node (ref "STM32F103C8T6") (pin "38") (pinfunction "+3.3V_38") (pintype "unspecified"))
    )
    (net (code "22") (name "GND") (class "Default")
      (node (ref "BAT") (pin "2") (pinfunction "2_2") (pintype "unspecified"))
      (node (ref "C10") (pin "1") (pinfunction "1_1") (pintype "unspecified"))
      (node (ref "C12") (pin "1") (pinfunction "1_1") (pintype "unspecified"))
      (node (ref "C17") (pin "2") (pinfunction "2_2") (pintype "unspecified"))
      (node (ref "C19") (pin "1") (pinfunction "1_1") (pintype "unspecified"))
      (node (ref "C2") (pin "2") (pinfunction "2_2") (pintype "input"))
      (node (ref "C3") (pin "1") (pinfunction "1_1") (pintype "input"))
      (node (ref "C4") (pin "1") (pinfunction "1_1") (pintype "unspecified"))
      (node (ref "C6") (pin "1") (pinfunction "1_1") (pintype "unspecified"))
      (node (ref "C7") (pin "1") (pinfunction "1_1") (pintype "unspecified"))
      (node (ref "C8") (pin "1") (pinfunction "1_1") (pintype "unspecified"))
      (node (ref "C9") (pin "1") (pinfunction "1_1") (pintype "unspecified"))
      (node (ref "H1") (pin "3") (pinfunction "3_3") (pintype "unspecified"))
      (node (ref "H1") (pin "4") (pinfunction "4_4") (pintype "unspecified"))
      (node (ref "OLED") (pin "1") (pinfunction "GND_1") (pintype "unspecified"))
      (node (ref "Q1") (pin "3") (pinfunction "E_3") (pintype "unspecified"))
      (node (ref "Q9") (pin "3") (pinfunction "E_3") (pintype "unspecified"))
      (node (ref "R10") (pin "2") (pinfunction "2_2") (pintype "unspecified"))
      (node (ref "R12") (pin "1") (pinfunction "1_1") (pintype "unspecified"))
      (node (ref "R17") (pin "1") (pinfunction "1_1") (pintype "unspecified"))
      (node (ref "R20") (pin "2") (pinfunction "2_2") (pintype "unspecified"))
      (node (ref "R32") (pin "2") (pinfunction "2_2") (pintype "unspecified"))
      (node (ref "R7") (pin "2") (pinfunction "2_2") (pintype "unspecified"))
      (node (ref "R8") (pin "1") (pinfunction "1_1") (pintype "unspecified"))
      (node (ref "R9") (pin "2") (pinfunction "2_2") (pintype "unspecified"))
      (node (ref "STM32F103C8T6") (pin "19") (pinfunction "GND_19") (pintype "unspecified"))
      (node (ref "STM32F103C8T6") (pin "39") (pinfunction "GND_39") (pintype "unspecified"))
      (node (ref "STM32F103C8T6") (pin "40") (pinfunction "GND_40") (pintype "unspecified"))
      (node (ref "SW1") (pin "1") (pinfunction "A_1") (pintype "unspecified"))
      (node (ref "SW1") (pin "2") (pinfunction "B_2") (pintype "unspecified"))
      (node (ref "SW2") (pin "1") (pinfunction "A_1") (pintype "unspecified"))
      (node (ref "SW2") (pin "2") (pinfunction "B_2") (pintype "unspecified"))
      (node (ref "SW3") (pin "1") (pinfunction "A_1") (pintype "unspecified"))
      (node (ref "SW3") (pin "2") (pinfunction "B_2") (pintype "unspecified"))
      (node (ref "SW4") (pin "1") (pinfunction "A_1") (pintype "unspecified"))
      (node (ref "SW4") (pin "2") (pinfunction "B_2") (pintype "unspecified"))
      (node (ref "U1") (pin "3") (pinfunction "GND_3") (pintype "unspecified"))
    )
    (net (code "23") (name "Net-(LED_Header-Pad2)") (class "Default")
      (node (ref "LED_Header") (pin "2") (pinfunction "2_2") (pintype "unspecified"))
      (node (ref "R31") (pin "2") (pinfunction "2_2") (pintype "unspecified"))
    )
    (net (code "24") (name "Net-(Q1-B)") (class "Default")
      (node (ref "Q1") (pin "2") (pinfunction "B_2") (pintype "unspecified"))
      (node (ref "R1") (pin "2") (pinfunction "2_2") (pintype "unspecified"))
    )
    (net (code "25") (name "Net-(Q2-D)") (class "Default")
      (node (ref "Q2") (pin "2") (pinfunction "D_2") (pintype "unspecified"))
      (node (ref "R31") (pin "1") (pinfunction "1_1") (pintype "unspecified"))
    )
    (net (code "26") (name "Net-(Q2-G)") (class "Default")
      (node (ref "Q2") (pin "1") (pinfunction "G_1") (pintype "unspecified"))
      (node (ref "R6") (pin "2") (pinfunction "2_2") (pintype "unspecified"))
    )
    (net (code "27") (name "Net-(Q2-S)") (class "Default")
      (node (ref "Q2") (pin "3") (pinfunction "S_3") (pintype "unspecified"))
      (node (ref "R4") (pin "2") (pinfunction "2_2") (pintype "unspecified"))
      (node (ref "R8") (pin "2") (pinfunction "2_2") (pintype "unspecified"))
    )
    (net (code "28") (name "Net-(Q9-B)") (class "Default")
      (node (ref "Q9") (pin "2") (pinfunction "B_2") (pintype "unspecified"))
      (node (ref "R30") (pin "1") (pinfunction "1_1") (pintype "unspecified"))
    )
    (net (code "29") (name "Net-(SW1-C)") (class "Default")
      (node (ref "C7") (pin "2") (pinfunction "2_2") (pintype "unspecified"))
      (node (ref "R21") (pin "1") (pinfunction "1_1") (pintype "unspecified"))
      (node (ref "SW1") (pin "3") (pinfunction "C_3") (pintype "unspecified"))
      (node (ref "SW1") (pin "4") (pinfunction "D_4") (pintype "unspecified"))
    )
    (net (code "30") (name "Net-(SW2-C)") (class "Default")
      (node (ref "C8") (pin "2") (pinfunction "2_2") (pintype "unspecified"))
      (node (ref "R22") (pin "1") (pinfunction "1_1") (pintype "unspecified"))
      (node (ref "SW2") (pin "3") (pinfunction "C_3") (pintype "unspecified"))
      (node (ref "SW2") (pin "4") (pinfunction "D_4") (pintype "unspecified"))
    )
    (net (code "31") (name "Net-(SW3-C)") (class "Default")
      (node (ref "C9") (pin "2") (pinfunction "2_2") (pintype "unspecified"))
      (node (ref "R24") (pin "1") (pinfunction "1_1") (pintype "unspecified"))
      (node (ref "SW3") (pin "3") (pinfunction "C_3") (pintype "unspecified"))
      (node (ref "SW3") (pin "4") (pinfunction "D_4") (pintype "unspecified"))
    )
    (net (code "32") (name "Net-(SW4-C)") (class "Default")
      (node (ref "C10") (pin "2") (pinfunction "2_2") (pintype "unspecified"))
      (node (ref "R27") (pin "1") (pinfunction "1_1") (pintype "unspecified"))
      (node (ref "SW4") (pin "3") (pinfunction "C_3") (pintype "unspecified"))
      (node (ref "SW4") (pin "4") (pinfunction "D_4") (pintype "unspecified"))
    )
    (net (code "33") (name "Net-(U1-CAP+)") (class "Default")
      (node (ref "C1") (pin "1") (pinfunction "1_1") (pintype "input"))
      (node (ref "U1") (pin "2") (pinfunction "CAP+_2") (pintype "unspecified"))
    )
    (net (code "34") (name "Net-(U1-CAP-)") (class "Default")
      (node (ref "C1") (pin "2") (pinfunction "2_2") (pintype "input"))
      (node (ref "U1") (pin "4") (pinfunction "CAP-_4") (pintype "unspecified"))
    )
    (net (code "35") (name "Net-(U3A-IN1+)") (class "Default")
      (node (ref "R17") (pin "2") (pinfunction "2_2") (pintype "unspecified"))
      (node (ref "R20") (pin "1") (pinfunction "1_1") (pintype "unspecified"))
      (node (ref "U3") (pin "3") (pinfunction "IN1+_3") (pintype "unspecified"))
    )
    (net (code "36") (name "Net-(U3A-IN1-)") (class "Default")
      (node (ref "R16") (pin "2") (pinfunction "2_2") (pintype "unspecified"))
      (node (ref "R18") (pin "1") (pinfunction "1_1") (pintype "unspecified"))
      (node (ref "U3") (pin "2") (pinfunction "IN1-_2") (pintype "unspecified"))
    )
    (net (code "37") (name "Net-(U3A-OUT1)") (class "Default")
      (node (ref "R18") (pin "2") (pinfunction "2_2") (pintype "unspecified"))
      (node (ref "R19") (pin "1") (pinfunction "1_1") (pintype "unspecified"))
      (node (ref "U3") (pin "1") (pinfunction "OUT1_1") (pintype "output"))
    )
    (net (code "38") (name "Net-(U3B-IN2+)") (class "Default")
      (node (ref "R4") (pin "1") (pinfunction "1_1") (pintype "unspecified"))
      (node (ref "U3") (pin "5") (pinfunction "IN2+_5") (pintype "unspecified"))
    )
    (net (code "39") (name "Net-(U3B-IN2-)") (class "Default")
      (node (ref "R5") (pin "2") (pinfunction "2_2") (pintype "unspecified"))
      (node (ref "R7") (pin "1") (pinfunction "1_1") (pintype "unspecified"))
      (node (ref "U3") (pin "6") (pinfunction "IN2-_6") (pintype "unspecified"))
    )
    (net (code "40") (name "Net-(U3B-OUT2)") (class "Default")
      (node (ref "R3") (pin "2") (pinfunction "2_2") (pintype "unspecified"))
      (node (ref "R5") (pin "1") (pinfunction "1_1") (pintype "unspecified"))
      (node (ref "U3") (pin "7") (pinfunction "OUT2_7") (pintype "output"))
    )
    (net (code "41") (name "unconnected-(STM32F103C8T6-PA1-Pad26)") (class "Default")
      (node (ref "STM32F103C8T6") (pin "26") (pinfunction "PA1_26") (pintype "unspecified"))
    )
    (net (code "42") (name "unconnected-(STM32F103C8T6-PA4-Pad29)") (class "Default")
      (node (ref "STM32F103C8T6") (pin "29") (pinfunction "PA4_29") (pintype "unspecified"))
    )
    (net (code "43") (name "unconnected-(STM32F103C8T6-PA5-Pad30)") (class "Default")
      (node (ref "STM32F103C8T6") (pin "30") (pinfunction "PA5_30") (pintype "unspecified"))
    )
    (net (code "44") (name "unconnected-(STM32F103C8T6-PA6-Pad31)") (class "Default")
      (node (ref "STM32F103C8T6") (pin "31") (pinfunction "PA6_31") (pintype "unspecified"))
    )
    (net (code "45") (name "unconnected-(STM32F103C8T6-PA7-Pad32)") (class "Default")
      (node (ref "STM32F103C8T6") (pin "32") (pinfunction "PA7_32") (pintype "unspecified"))
    )
    (net (code "46") (name "unconnected-(STM32F103C8T6-PA8-Pad5)") (class "Default")
      (node (ref "STM32F103C8T6") (pin "5") (pinfunction "PA8_5") (pintype "unspecified"))
    )
    (net (code "47") (name "unconnected-(STM32F103C8T6-PA11-Pad8)") (class "Default")
      (node (ref "STM32F103C8T6") (pin "8") (pinfunction "PA11_8") (pintype "unspecified"))
    )
    (net (code "48") (name "unconnected-(STM32F103C8T6-PA12-Pad9)") (class "Default")
      (node (ref "STM32F103C8T6") (pin "9") (pinfunction "PA12_9") (pintype "unspecified"))
    )
    (net (code "49") (name "unconnected-(STM32F103C8T6-PA15-Pad10)") (class "Default")
      (node (ref "STM32F103C8T6") (pin "10") (pinfunction "PA15_10") (pintype "unspecified"))
    )
    (net (code "50") (name "unconnected-(STM32F103C8T6-PB3-Pad11)") (class "Default")
      (node (ref "STM32F103C8T6") (pin "11") (pinfunction "PB3_11") (pintype "unspecified"))
    )
    (net (code "51") (name "unconnected-(STM32F103C8T6-PB4-Pad12)") (class "Default")
      (node (ref "STM32F103C8T6") (pin "12") (pinfunction "PB4_12") (pintype "unspecified"))
    )
    (net (code "52") (name "unconnected-(STM32F103C8T6-PB9-Pad17)") (class "Default")
      (node (ref "STM32F103C8T6") (pin "17") (pinfunction "PB9_17") (pintype "unspecified"))
    )
    (net (code "53") (name "unconnected-(STM32F103C8T6-PB12-Pad1)") (class "Default")
      (node (ref "STM32F103C8T6") (pin "1") (pinfunction "PB12_1") (pintype "unspecified"))
    )
    (net (code "54") (name "unconnected-(STM32F103C8T6-PB13-Pad2)") (class "Default")
      (node (ref "STM32F103C8T6") (pin "2") (pinfunction "PB13_2") (pintype "unspecified"))
    )
    (net (code "55") (name "unconnected-(STM32F103C8T6-PB14-Pad3)") (class "Default")
      (node (ref "STM32F103C8T6") (pin "3") (pinfunction "PB14_3") (pintype "unspecified"))
    )
    (net (code "56") (name "unconnected-(STM32F103C8T6-PB15-Pad4)") (class "Default")
      (node (ref "STM32F103C8T6") (pin "4") (pinfunction "PB15_4") (pintype "unspecified"))
    )
    (net (code "57") (name "unconnected-(STM32F103C8T6-PC13-Pad22)") (class "Default")
      (node (ref "STM32F103C8T6") (pin "22") (pinfunction "PC13_22") (pintype "unspecified"))
    )
    (net (code "58") (name "unconnected-(STM32F103C8T6-PC14-Pad23)") (class "Default")
      (node (ref "STM32F103C8T6") (pin "23") (pinfunction "PC14_23") (pintype "unspecified"))
    )
    (net (code "59") (name "unconnected-(STM32F103C8T6-PC15-Pad24)") (class "Default")
      (node (ref "STM32F103C8T6") (pin "24") (pinfunction "PC15_24") (pintype "unspecified"))
    )
    (net (code "60") (name "unconnected-(STM32F103C8T6-RESET-Pad37)") (class "Default")
      (node (ref "STM32F103C8T6") (pin "37") (pinfunction "RESET_37") (pintype "unspecified"))
    )
    (net (code "61") (name "unconnected-(STM32F103C8T6-VBAT-Pad21)") (class "Default")
      (node (ref "STM32F103C8T6") (pin "21") (pinfunction "VBAT_21") (pintype "unspecified"))
    )
    (net (code "62") (name "unconnected-(U1-LV-Pad6)") (class "Default")
      (node (ref "U1") (pin "6") (pinfunction "LV_6") (pintype "unspecified+no_connect"))
    )
    (net (code "63") (name "unconnected-(U1-NC-Pad1)") (class "Default")
      (node (ref "U1") (pin "1") (pinfunction "NC_1") (pintype "unspecified+no_connect"))
    )
    (net (code "64") (name "unconnected-(U1-OBC-Pad7)") (class "Default")
      (node (ref "U1") (pin "7") (pinfunction "OBC_7") (pintype "unspecified+no_connect"))
    )
  )
)
